# ZynqPS.net
KiCad netlist of a schematic drawn in Altium Designer
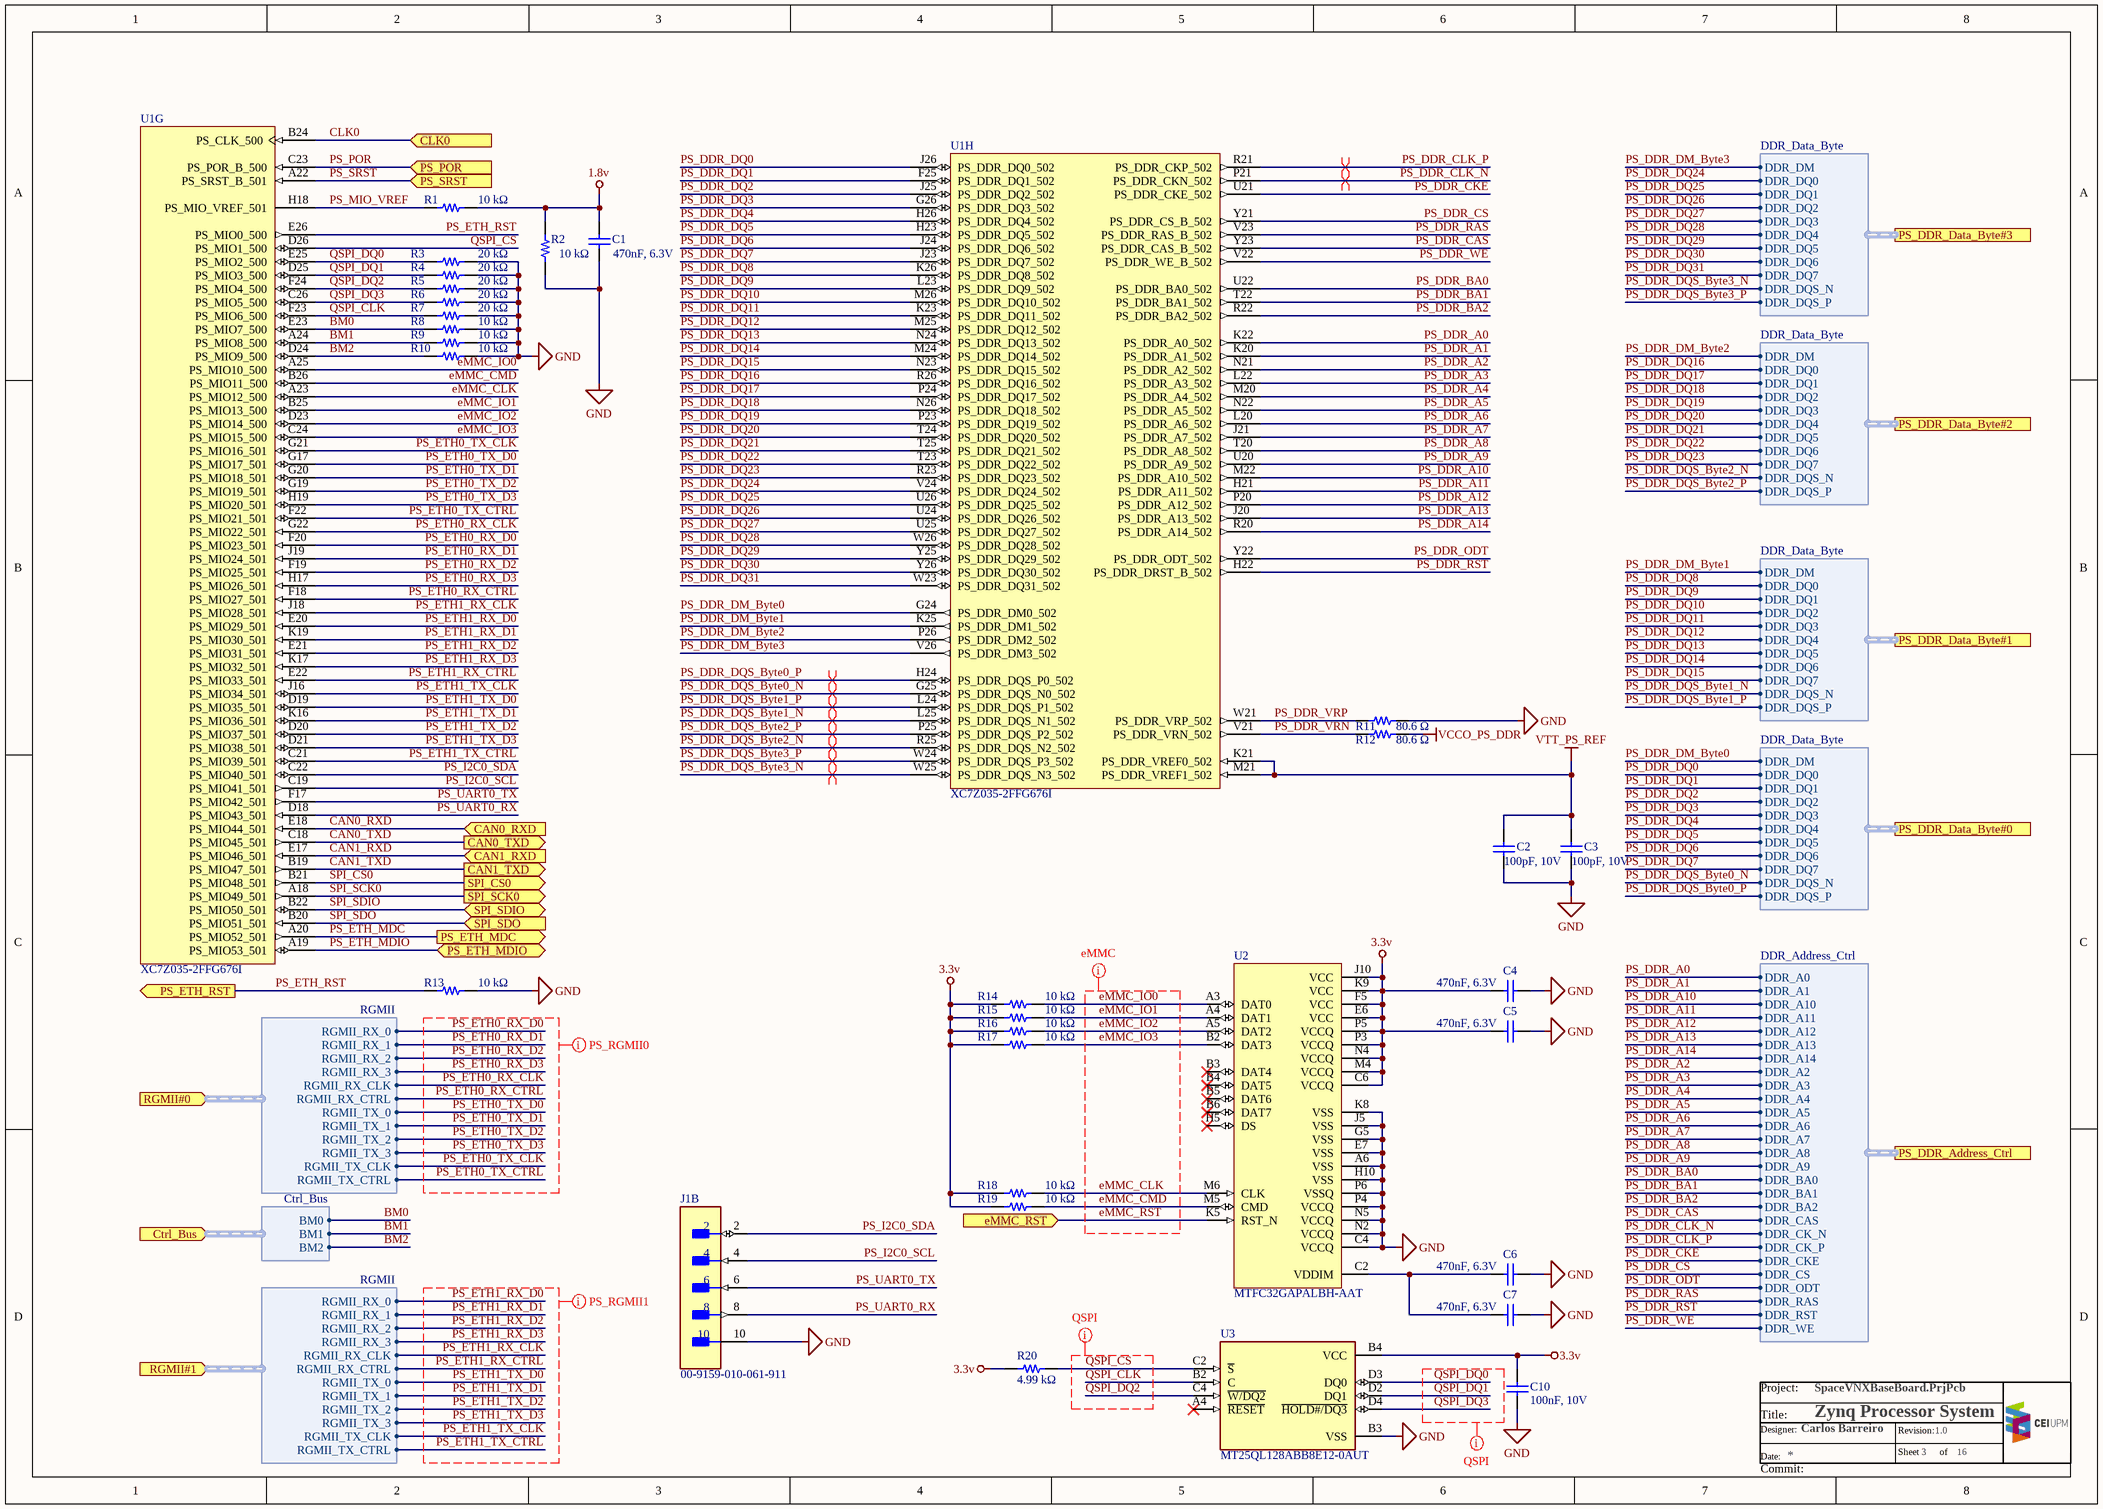
[diagram p0: ZynqPS.SchDoc]

(export (version "E")
  (design (tool "Eeschema 10.0.6"))
  (components
    (comp (ref "C1")
      (value "470nF, 6.3V")
      (footprint "WURTH_WCAP-CSGP_0402")
      (description "WCAP-CSGP Multilayer Ceramic Chip Capacitor, General Purpose, size 0402, X5R, 470nF, 6.3V")
      (fields
        (field (name "MANUFACTURER PART NUMBER") "885012105004")
        (field (name "MANUFACTURER") "Wurth Elektronik")
      )
      (libsource (lib "SpaceVNX") (part "885012105004"))
    )
    (comp (ref "C2")
      (value "100pF, 10V")
      (footprint "WURTH_WCAP-CSGP_0402")
      (description "WCAP-CSGP Multilayer Ceramic Chip Capacitor, General Purpose, size 0402, NP0, 100pF, 10V")
      (fields
        (field (name "MANUFACTURER PART NUMBER") "885012005013")
        (field (name "MANUFACTURER") "Wurth Elektronik")
      )
      (libsource (lib "SpaceVNX") (part "885012005013"))
    )
    (comp (ref "C3")
      (value "100pF, 10V")
      (footprint "WURTH_WCAP-CSGP_0402")
      (description "WCAP-CSGP Multilayer Ceramic Chip Capacitor, General Purpose, size 0402, NP0, 100pF, 10V")
      (fields
        (field (name "MANUFACTURER PART NUMBER") "885012005013")
        (field (name "MANUFACTURER") "Wurth Elektronik")
      )
      (libsource (lib "SpaceVNX") (part "885012005013"))
    )
    (comp (ref "C4")
      (value "470nF, 6.3V")
      (footprint "WURTH_WCAP-CSGP_0402")
      (description "WCAP-CSGP Multilayer Ceramic Chip Capacitor, General Purpose, size 0402, X5R, 470nF, 6.3V")
      (fields
        (field (name "MANUFACTURER PART NUMBER") "885012105004")
        (field (name "MANUFACTURER") "Wurth Elektronik")
      )
      (libsource (lib "SpaceVNX") (part "885012105004"))
    )
    (comp (ref "C5")
      (value "470nF, 6.3V")
      (footprint "WURTH_WCAP-CSGP_0402")
      (description "WCAP-CSGP Multilayer Ceramic Chip Capacitor, General Purpose, size 0402, X5R, 470nF, 6.3V")
      (fields
        (field (name "MANUFACTURER PART NUMBER") "885012105004")
        (field (name "MANUFACTURER") "Wurth Elektronik")
      )
      (libsource (lib "SpaceVNX") (part "885012105004"))
    )
    (comp (ref "C6")
      (value "470nF, 6.3V")
      (footprint "WURTH_WCAP-CSGP_0402")
      (description "WCAP-CSGP Multilayer Ceramic Chip Capacitor, General Purpose, size 0402, X5R, 470nF, 6.3V")
      (fields
        (field (name "MANUFACTURER PART NUMBER") "885012105004")
        (field (name "MANUFACTURER") "Wurth Elektronik")
      )
      (libsource (lib "SpaceVNX") (part "885012105004"))
    )
    (comp (ref "C7")
      (value "470nF, 6.3V")
      (footprint "WURTH_WCAP-CSGP_0402")
      (description "WCAP-CSGP Multilayer Ceramic Chip Capacitor, General Purpose, size 0402, X5R, 470nF, 6.3V")
      (fields
        (field (name "MANUFACTURER PART NUMBER") "885012105004")
        (field (name "MANUFACTURER") "Wurth Elektronik")
      )
      (libsource (lib "SpaceVNX") (part "885012105004"))
    )
    (comp (ref "C10")
      (value "100nF, 10V")
      (footprint "WURTH_WCAP-CSGP_0402")
      (description "WCAP-CSGP Multilayer Ceramic Chip Capacitor, General Purpose, size 0402, X7R, 100nF, 10V")
      (fields
        (field (name "MANUFACTURER PART NUMBER") "885012205018")
        (field (name "MANUFACTURER") "Wurth Elektronik")
      )
      (libsource (lib "SpaceVNX") (part "885012205018"))
    )
    (comp (ref "J1")
      (value "00-9159-010-061-911")
      (footprint "KYOCERA_00-9159-010-061-911")
      (description "Coplanar Open Ended Card Edge Connector 10 Pin")
      (libsource (lib "SpaceVNX") (part "00-9159-010-061-911"))
    )
    (comp (ref "R1")
      (value "10 kΩ")
      (footprint "PANASONIC_ERJ2G_0402")
      (description "General Purpose Thick Film Chip Resistors")
      (fields (field (name "MANUFACTURER") "Panasonic"))
      (libsource (lib "SpaceVNX") (part "ERJ2RKF1002X"))
    )
    (comp (ref "R2")
      (value "10 kΩ")
      (footprint "PANASONIC_ERJ2G_0402")
      (description "General Purpose Thick Film Chip Resistors")
      (fields (field (name "MANUFACTURER") "Panasonic"))
      (libsource (lib "SpaceVNX") (part "ERJ2RKF1002X"))
    )
    (comp (ref "R3")
      (value "20 kΩ")
      (footprint "PANASONIC_ERJ2G_0402")
      (description "General Purpose Thick Film Chip Resistors")
      (fields (field (name "MANUFACTURER") "Panasonic"))
      (libsource (lib "SpaceVNX") (part "ERJ2RKF2002X"))
    )
    (comp (ref "R4")
      (value "20 kΩ")
      (footprint "PANASONIC_ERJ2G_0402")
      (description "General Purpose Thick Film Chip Resistors")
      (fields (field (name "MANUFACTURER") "Panasonic"))
      (libsource (lib "SpaceVNX") (part "ERJ2RKF2002X"))
    )
    (comp (ref "R5")
      (value "20 kΩ")
      (footprint "PANASONIC_ERJ2G_0402")
      (description "General Purpose Thick Film Chip Resistors")
      (fields (field (name "MANUFACTURER") "Panasonic"))
      (libsource (lib "SpaceVNX") (part "ERJ2RKF2002X"))
    )
    (comp (ref "R6")
      (value "20 kΩ")
      (footprint "PANASONIC_ERJ2G_0402")
      (description "General Purpose Thick Film Chip Resistors")
      (fields (field (name "MANUFACTURER") "Panasonic"))
      (libsource (lib "SpaceVNX") (part "ERJ2RKF2002X"))
    )
    (comp (ref "R7")
      (value "20 kΩ")
      (footprint "PANASONIC_ERJ2G_0402")
      (description "General Purpose Thick Film Chip Resistors")
      (fields (field (name "MANUFACTURER") "Panasonic"))
      (libsource (lib "SpaceVNX") (part "ERJ2RKF2002X"))
    )
    (comp (ref "R8")
      (value "10 kΩ")
      (footprint "PANASONIC_ERJ2G_0402")
      (description "General Purpose Thick Film Chip Resistors")
      (fields (field (name "MANUFACTURER") "Panasonic"))
      (libsource (lib "SpaceVNX") (part "ERJ2RKF1002X"))
    )
    (comp (ref "R9")
      (value "10 kΩ")
      (footprint "PANASONIC_ERJ2G_0402")
      (description "General Purpose Thick Film Chip Resistors")
      (fields (field (name "MANUFACTURER") "Panasonic"))
      (libsource (lib "SpaceVNX") (part "ERJ2RKF1002X"))
    )
    (comp (ref "R10")
      (value "10 kΩ")
      (footprint "PANASONIC_ERJ2G_0402")
      (description "General Purpose Thick Film Chip Resistors")
      (fields (field (name "MANUFACTURER") "Panasonic"))
      (libsource (lib "SpaceVNX") (part "ERJ2RKF1002X"))
    )
    (comp (ref "R11")
      (value "80.6 Ω")
      (footprint "PANASONIC_ERJ2G_0402")
      (description "General Purpose Thick Film Chip Resistors")
      (fields (field (name "MANUFACTURER") "Panasonic"))
      (libsource (lib "SpaceVNX") (part "ERJ2RKF80R6X"))
    )
    (comp (ref "R12")
      (value "80.6 Ω")
      (footprint "PANASONIC_ERJ2G_0402")
      (description "General Purpose Thick Film Chip Resistors")
      (fields (field (name "MANUFACTURER") "Panasonic"))
      (libsource (lib "SpaceVNX") (part "ERJ2RKF80R6X"))
    )
    (comp (ref "R13")
      (value "10 kΩ")
      (footprint "PANASONIC_ERJ2G_0402")
      (description "General Purpose Thick Film Chip Resistors")
      (fields (field (name "MANUFACTURER") "Panasonic"))
      (libsource (lib "SpaceVNX") (part "ERJ2RKF1002X"))
    )
    (comp (ref "R14")
      (value "10 kΩ")
      (footprint "PANASONIC_ERJ2G_0402")
      (description "General Purpose Thick Film Chip Resistors")
      (fields (field (name "MANUFACTURER") "Panasonic"))
      (libsource (lib "SpaceVNX") (part "ERJ2RKF1002X"))
    )
    (comp (ref "R15")
      (value "10 kΩ")
      (footprint "PANASONIC_ERJ2G_0402")
      (description "General Purpose Thick Film Chip Resistors")
      (fields (field (name "MANUFACTURER") "Panasonic"))
      (libsource (lib "SpaceVNX") (part "ERJ2RKF1002X"))
    )
    (comp (ref "R16")
      (value "10 kΩ")
      (footprint "PANASONIC_ERJ2G_0402")
      (description "General Purpose Thick Film Chip Resistors")
      (fields (field (name "MANUFACTURER") "Panasonic"))
      (libsource (lib "SpaceVNX") (part "ERJ2RKF1002X"))
    )
    (comp (ref "R17")
      (value "10 kΩ")
      (footprint "PANASONIC_ERJ2G_0402")
      (description "General Purpose Thick Film Chip Resistors")
      (fields (field (name "MANUFACTURER") "Panasonic"))
      (libsource (lib "SpaceVNX") (part "ERJ2RKF1002X"))
    )
    (comp (ref "R18")
      (value "10 kΩ")
      (footprint "PANASONIC_ERJ2G_0402")
      (description "General Purpose Thick Film Chip Resistors")
      (fields (field (name "MANUFACTURER") "Panasonic"))
      (libsource (lib "SpaceVNX") (part "ERJ2RKF1002X"))
    )
    (comp (ref "R19")
      (value "10 kΩ")
      (footprint "PANASONIC_ERJ2G_0402")
      (description "General Purpose Thick Film Chip Resistors")
      (fields (field (name "MANUFACTURER") "Panasonic"))
      (libsource (lib "SpaceVNX") (part "ERJ2RKF1002X"))
    )
    (comp (ref "R20")
      (value "4.99 kΩ")
      (footprint "PANASONIC_ERJ2G_0402")
      (description "General Purpose Thick Film Chip Resistors")
      (fields (field (name "MANUFACTURER") "Panasonic"))
      (libsource (lib "SpaceVNX") (part "ERJ2RKF4991X"))
    )
    (comp (ref "U1")
      (value "XC7Z035-2FFG676I")
      (footprint "XILINX_FBG676")
      (fields (field (name "PARTNUMBER") "XC7Z035-2FBG676I") (field (name "GENERIC PART NUMBER") "XC7Z035"))
      (libsource (lib "SpaceVNX") (part "XC7Z035-2FFG676I"))
    )
    (comp (ref "U2")
      (value "MTFC32GAPALBH-AAT")
      (footprint "Micron_BH")
      (description "Flash Memory Managed NAND e.MMC Automotive 32GB")
      (fields (field (name "MF") "Micron Technology"))
      (libsource (lib "SpaceVNX") (part "MTFC32GAPALBH-AAT"))
    )
    (comp (ref "U3")
      (value "MT25QL128ABB8E12-0AUT")
      (footprint "Micron_RW")
      (description "NOR Serial Flash Memory 128Mb 3.3V Multiple I/O Automotive")
      (fields (field (name "MF") "Micron Technology"))
      (libsource (lib "SpaceVNX") (part "MT25QL128ABB8E12-0AUT"))
    )
  )
  (nets
    (net (code "5") (name "/BM0") (class "Default")
      (node (ref "R8") (pin "2") (pinfunction "2_2") (pintype "passive"))
      (node (ref "U1") (pin "E23") (pinfunction "PS_MIO7_500_E23") (pintype "bidirectional"))
    )
    (net (code "6") (name "/BM1") (class "Default")
      (node (ref "R9") (pin "2") (pinfunction "2_2") (pintype "passive"))
      (node (ref "U1") (pin "A24") (pinfunction "PS_MIO8_500_A24") (pintype "bidirectional"))
    )
    (net (code "7") (name "/BM2") (class "Default")
      (node (ref "R10") (pin "2") (pinfunction "2_2") (pintype "passive"))
      (node (ref "U1") (pin "D24") (pinfunction "PS_MIO9_500_D24") (pintype "bidirectional"))
    )
    (net (code "8") (name "/CAN0_RXD") (class "Default")
      (node (ref "U1") (pin "E18") (pinfunction "PS_MIO44_501_E18") (pintype "input"))
    )
    (net (code "9") (name "/CAN0_TXD") (class "Default")
      (node (ref "U1") (pin "C18") (pinfunction "PS_MIO45_501_C18") (pintype "output"))
    )
    (net (code "10") (name "/CAN1_RXD") (class "Default")
      (node (ref "U1") (pin "E17") (pinfunction "PS_MIO46_501_E17") (pintype "input"))
    )
    (net (code "11") (name "/CAN1_TXD") (class "Default")
      (node (ref "U1") (pin "B19") (pinfunction "PS_MIO47_501_B19") (pintype "output"))
    )
    (net (code "12") (name "/CLK0") (class "Default")
      (node (ref "U1") (pin "B24") (pinfunction "PS_CLK_500_B24") (pintype "input"))
    )
    (net (code "13") (name "/PS_DDR_A0") (class "Default")
      (node (ref "U1") (pin "K22") (pinfunction "PS_DDR_A0_502_K22") (pintype "output"))
    )
    (net (code "14") (name "/PS_DDR_A1") (class "Default")
      (node (ref "U1") (pin "K20") (pinfunction "PS_DDR_A1_502_K20") (pintype "output"))
    )
    (net (code "15") (name "/PS_DDR_A2") (class "Default")
      (node (ref "U1") (pin "N21") (pinfunction "PS_DDR_A2_502_N21") (pintype "output"))
    )
    (net (code "16") (name "/PS_DDR_A3") (class "Default")
      (node (ref "U1") (pin "L22") (pinfunction "PS_DDR_A3_502_L22") (pintype "output"))
    )
    (net (code "17") (name "/PS_DDR_A4") (class "Default")
      (node (ref "U1") (pin "M20") (pinfunction "PS_DDR_A4_502_M20") (pintype "output"))
    )
    (net (code "18") (name "/PS_DDR_A5") (class "Default")
      (node (ref "U1") (pin "N22") (pinfunction "PS_DDR_A5_502_N22") (pintype "output"))
    )
    (net (code "19") (name "/PS_DDR_A6") (class "Default")
      (node (ref "U1") (pin "L20") (pinfunction "PS_DDR_A6_502_L20") (pintype "output"))
    )
    (net (code "20") (name "/PS_DDR_A7") (class "Default")
      (node (ref "U1") (pin "J21") (pinfunction "PS_DDR_A7_502_J21") (pintype "output"))
    )
    (net (code "21") (name "/PS_DDR_A8") (class "Default")
      (node (ref "U1") (pin "T20") (pinfunction "PS_DDR_A8_502_T20") (pintype "output"))
    )
    (net (code "22") (name "/PS_DDR_A9") (class "Default")
      (node (ref "U1") (pin "U20") (pinfunction "PS_DDR_A9_502_U20") (pintype "output"))
    )
    (net (code "23") (name "/PS_DDR_A10") (class "Default")
      (node (ref "U1") (pin "M22") (pinfunction "PS_DDR_A10_502_M22") (pintype "output"))
    )
    (net (code "24") (name "/PS_DDR_A11") (class "Default")
      (node (ref "U1") (pin "H21") (pinfunction "PS_DDR_A11_502_H21") (pintype "output"))
    )
    (net (code "25") (name "/PS_DDR_A12") (class "Default")
      (node (ref "U1") (pin "P20") (pinfunction "PS_DDR_A12_502_P20") (pintype "output"))
    )
    (net (code "26") (name "/PS_DDR_A13") (class "Default")
      (node (ref "U1") (pin "J20") (pinfunction "PS_DDR_A13_502_J20") (pintype "output"))
    )
    (net (code "27") (name "/PS_DDR_A14") (class "Default")
      (node (ref "U1") (pin "R20") (pinfunction "PS_DDR_A14_502_R20") (pintype "output"))
    )
    (net (code "28") (name "/PS_DDR_BA0") (class "Default")
      (node (ref "U1") (pin "U22") (pinfunction "PS_DDR_BA0_502_U22") (pintype "output"))
    )
    (net (code "29") (name "/PS_DDR_BA1") (class "Default")
      (node (ref "U1") (pin "T22") (pinfunction "PS_DDR_BA1_502_T22") (pintype "output"))
    )
    (net (code "30") (name "/PS_DDR_BA2") (class "Default")
      (node (ref "U1") (pin "R22") (pinfunction "PS_DDR_BA2_502_R22") (pintype "output"))
    )
    (net (code "31") (name "/PS_DDR_CAS") (class "Default")
      (node (ref "U1") (pin "Y23") (pinfunction "PS_DDR_CAS_B_502_Y23") (pintype "output"))
    )
    (net (code "32") (name "/PS_DDR_CKE") (class "Default")
      (node (ref "U1") (pin "U21") (pinfunction "PS_DDR_CKE_502_U21") (pintype "output"))
    )
    (net (code "33") (name "/PS_DDR_CLK_N") (class "Default")
      (node (ref "U1") (pin "P21") (pinfunction "PS_DDR_CKN_502_P21") (pintype "output"))
    )
    (net (code "34") (name "/PS_DDR_CLK_P") (class "Default")
      (node (ref "U1") (pin "R21") (pinfunction "PS_DDR_CKP_502_R21") (pintype "output"))
    )
    (net (code "35") (name "/PS_DDR_CS") (class "Default")
      (node (ref "U1") (pin "Y21") (pinfunction "PS_DDR_CS_B_502_Y21") (pintype "output"))
    )
    (net (code "36") (name "/PS_DDR_DM_Byte0") (class "Default")
      (node (ref "U1") (pin "G24") (pinfunction "PS_DDR_DM0_502_G24") (pintype "output"))
    )
    (net (code "37") (name "/PS_DDR_DM_Byte1") (class "Default")
      (node (ref "U1") (pin "K25") (pinfunction "PS_DDR_DM1_502_K25") (pintype "output"))
    )
    (net (code "38") (name "/PS_DDR_DM_Byte2") (class "Default")
      (node (ref "U1") (pin "P26") (pinfunction "PS_DDR_DM2_502_P26") (pintype "output"))
    )
    (net (code "39") (name "/PS_DDR_DM_Byte3") (class "Default")
      (node (ref "U1") (pin "V26") (pinfunction "PS_DDR_DM3_502_V26") (pintype "output"))
    )
    (net (code "40") (name "/PS_DDR_DQ0") (class "Default")
      (node (ref "U1") (pin "J26") (pinfunction "PS_DDR_DQ0_502_J26") (pintype "bidirectional"))
    )
    (net (code "41") (name "/PS_DDR_DQ1") (class "Default")
      (node (ref "U1") (pin "F25") (pinfunction "PS_DDR_DQ1_502_F25") (pintype "bidirectional"))
    )
    (net (code "42") (name "/PS_DDR_DQ2") (class "Default")
      (node (ref "U1") (pin "J25") (pinfunction "PS_DDR_DQ2_502_J25") (pintype "bidirectional"))
    )
    (net (code "43") (name "/PS_DDR_DQ3") (class "Default")
      (node (ref "U1") (pin "G26") (pinfunction "PS_DDR_DQ3_502_G26") (pintype "bidirectional"))
    )
    (net (code "44") (name "/PS_DDR_DQ4") (class "Default")
      (node (ref "U1") (pin "H26") (pinfunction "PS_DDR_DQ4_502_H26") (pintype "bidirectional"))
    )
    (net (code "45") (name "/PS_DDR_DQ5") (class "Default")
      (node (ref "U1") (pin "H23") (pinfunction "PS_DDR_DQ5_502_H23") (pintype "bidirectional"))
    )
    (net (code "46") (name "/PS_DDR_DQ6") (class "Default")
      (node (ref "U1") (pin "J24") (pinfunction "PS_DDR_DQ6_502_J24") (pintype "bidirectional"))
    )
    (net (code "47") (name "/PS_DDR_DQ7") (class "Default")
      (node (ref "U1") (pin "J23") (pinfunction "PS_DDR_DQ7_502_J23") (pintype "bidirectional"))
    )
    (net (code "48") (name "/PS_DDR_DQ8") (class "Default")
      (node (ref "U1") (pin "K26") (pinfunction "PS_DDR_DQ8_502_K26") (pintype "bidirectional"))
    )
    (net (code "49") (name "/PS_DDR_DQ9") (class "Default")
      (node (ref "U1") (pin "L23") (pinfunction "PS_DDR_DQ9_502_L23") (pintype "bidirectional"))
    )
    (net (code "50") (name "/PS_DDR_DQ10") (class "Default")
      (node (ref "U1") (pin "M26") (pinfunction "PS_DDR_DQ10_502_M26") (pintype "bidirectional"))
    )
    (net (code "51") (name "/PS_DDR_DQ11") (class "Default")
      (node (ref "U1") (pin "K23") (pinfunction "PS_DDR_DQ11_502_K23") (pintype "bidirectional"))
    )
    (net (code "52") (name "/PS_DDR_DQ12") (class "Default")
      (node (ref "U1") (pin "M25") (pinfunction "PS_DDR_DQ12_502_M25") (pintype "bidirectional"))
    )
    (net (code "53") (name "/PS_DDR_DQ13") (class "Default")
      (node (ref "U1") (pin "N24") (pinfunction "PS_DDR_DQ13_502_N24") (pintype "bidirectional"))
    )
    (net (code "54") (name "/PS_DDR_DQ14") (class "Default")
      (node (ref "U1") (pin "M24") (pinfunction "PS_DDR_DQ14_502_M24") (pintype "bidirectional"))
    )
    (net (code "55") (name "/PS_DDR_DQ15") (class "Default")
      (node (ref "U1") (pin "N23") (pinfunction "PS_DDR_DQ15_502_N23") (pintype "bidirectional"))
    )
    (net (code "56") (name "/PS_DDR_DQ16") (class "Default")
      (node (ref "U1") (pin "R26") (pinfunction "PS_DDR_DQ16_502_R26") (pintype "bidirectional"))
    )
    (net (code "57") (name "/PS_DDR_DQ17") (class "Default")
      (node (ref "U1") (pin "P24") (pinfunction "PS_DDR_DQ17_502_P24") (pintype "bidirectional"))
    )
    (net (code "58") (name "/PS_DDR_DQ18") (class "Default")
      (node (ref "U1") (pin "N26") (pinfunction "PS_DDR_DQ18_502_N26") (pintype "bidirectional"))
    )
    (net (code "59") (name "/PS_DDR_DQ19") (class "Default")
      (node (ref "U1") (pin "P23") (pinfunction "PS_DDR_DQ19_502_P23") (pintype "bidirectional"))
    )
    (net (code "60") (name "/PS_DDR_DQ20") (class "Default")
      (node (ref "U1") (pin "T24") (pinfunction "PS_DDR_DQ20_502_T24") (pintype "bidirectional"))
    )
    (net (code "61") (name "/PS_DDR_DQ21") (class "Default")
      (node (ref "U1") (pin "T25") (pinfunction "PS_DDR_DQ21_502_T25") (pintype "bidirectional"))
    )
    (net (code "62") (name "/PS_DDR_DQ22") (class "Default")
      (node (ref "U1") (pin "T23") (pinfunction "PS_DDR_DQ22_502_T23") (pintype "bidirectional"))
    )
    (net (code "63") (name "/PS_DDR_DQ23") (class "Default")
      (node (ref "U1") (pin "R23") (pinfunction "PS_DDR_DQ23_502_R23") (pintype "bidirectional"))
    )
    (net (code "64") (name "/PS_DDR_DQ24") (class "Default")
      (node (ref "U1") (pin "V24") (pinfunction "PS_DDR_DQ24_502_V24") (pintype "bidirectional"))
    )
    (net (code "65") (name "/PS_DDR_DQ25") (class "Default")
      (node (ref "U1") (pin "U26") (pinfunction "PS_DDR_DQ25_502_U26") (pintype "bidirectional"))
    )
    (net (code "66") (name "/PS_DDR_DQ26") (class "Default")
      (node (ref "U1") (pin "U24") (pinfunction "PS_DDR_DQ26_502_U24") (pintype "bidirectional"))
    )
    (net (code "67") (name "/PS_DDR_DQ27") (class "Default")
      (node (ref "U1") (pin "U25") (pinfunction "PS_DDR_DQ27_502_U25") (pintype "bidirectional"))
    )
    (net (code "68") (name "/PS_DDR_DQ28") (class "Default")
      (node (ref "U1") (pin "W26") (pinfunction "PS_DDR_DQ28_502_W26") (pintype "bidirectional"))
    )
    (net (code "69") (name "/PS_DDR_DQ29") (class "Default")
      (node (ref "U1") (pin "Y25") (pinfunction "PS_DDR_DQ29_502_Y25") (pintype "bidirectional"))
    )
    (net (code "70") (name "/PS_DDR_DQ30") (class "Default")
      (node (ref "U1") (pin "Y26") (pinfunction "PS_DDR_DQ30_502_Y26") (pintype "bidirectional"))
    )
    (net (code "71") (name "/PS_DDR_DQ31") (class "Default")
      (node (ref "U1") (pin "W23") (pinfunction "PS_DDR_DQ31_502_W23") (pintype "bidirectional"))
    )
    (net (code "72") (name "/PS_DDR_DQS_Byte0_N") (class "Default")
      (node (ref "U1") (pin "G25") (pinfunction "PS_DDR_DQS_N0_502_G25") (pintype "bidirectional"))
    )
    (net (code "73") (name "/PS_DDR_DQS_Byte0_P") (class "Default")
      (node (ref "U1") (pin "H24") (pinfunction "PS_DDR_DQS_P0_502_H24") (pintype "bidirectional"))
    )
    (net (code "74") (name "/PS_DDR_DQS_Byte1_N") (class "Default")
      (node (ref "U1") (pin "L25") (pinfunction "PS_DDR_DQS_N1_502_L25") (pintype "bidirectional"))
    )
    (net (code "75") (name "/PS_DDR_DQS_Byte1_P") (class "Default")
      (node (ref "U1") (pin "L24") (pinfunction "PS_DDR_DQS_P1_502_L24") (pintype "bidirectional"))
    )
    (net (code "76") (name "/PS_DDR_DQS_Byte2_N") (class "Default")
      (node (ref "U1") (pin "R25") (pinfunction "PS_DDR_DQS_N2_502_R25") (pintype "bidirectional"))
    )
    (net (code "77") (name "/PS_DDR_DQS_Byte2_P") (class "Default")
      (node (ref "U1") (pin "P25") (pinfunction "PS_DDR_DQS_P2_502_P25") (pintype "bidirectional"))
    )
    (net (code "78") (name "/PS_DDR_DQS_Byte3_N") (class "Default")
      (node (ref "U1") (pin "W25") (pinfunction "PS_DDR_DQS_N3_502_W25") (pintype "bidirectional"))
    )
    (net (code "79") (name "/PS_DDR_DQS_Byte3_P") (class "Default")
      (node (ref "U1") (pin "W24") (pinfunction "PS_DDR_DQS_P3_502_W24") (pintype "bidirectional"))
    )
    (net (code "80") (name "/PS_DDR_ODT") (class "Default")
      (node (ref "U1") (pin "Y22") (pinfunction "PS_DDR_ODT_502_Y22") (pintype "output"))
    )
    (net (code "81") (name "/PS_DDR_RAS") (class "Default")
      (node (ref "U1") (pin "V23") (pinfunction "PS_DDR_RAS_B_502_V23") (pintype "output"))
    )
    (net (code "82") (name "/PS_DDR_RST") (class "Default")
      (node (ref "U1") (pin "H22") (pinfunction "PS_DDR_DRST_B_502_H22") (pintype "output"))
    )
    (net (code "83") (name "/PS_DDR_VRN") (class "Default")
      (node (ref "R12") (pin "1") (pinfunction "1_1") (pintype "passive"))
      (node (ref "U1") (pin "V21") (pinfunction "PS_DDR_VRN_502_V21") (pintype "output"))
    )
    (net (code "84") (name "/PS_DDR_VRP") (class "Default")
      (node (ref "R11") (pin "1") (pinfunction "1_1") (pintype "passive"))
      (node (ref "U1") (pin "W21") (pinfunction "PS_DDR_VRP_502_W21") (pintype "output"))
    )
    (net (code "85") (name "/PS_DDR_WE") (class "Default")
      (node (ref "U1") (pin "V22") (pinfunction "PS_DDR_WE_B_502_V22") (pintype "output"))
    )
    (net (code "86") (name "/PS_ETH0_RX_CLK") (class "Default")
      (node (ref "U1") (pin "G22") (pinfunction "PS_MIO22_501_G22") (pintype "input"))
    )
    (net (code "87") (name "/PS_ETH0_RX_CTRL") (class "Default")
      (node (ref "U1") (pin "F18") (pinfunction "PS_MIO27_501_F18") (pintype "input"))
    )
    (net (code "88") (name "/PS_ETH0_RX_D0") (class "Default")
      (node (ref "U1") (pin "F20") (pinfunction "PS_MIO23_501_F20") (pintype "input"))
    )
    (net (code "89") (name "/PS_ETH0_RX_D1") (class "Default")
      (node (ref "U1") (pin "J19") (pinfunction "PS_MIO24_501_J19") (pintype "input"))
    )
    (net (code "90") (name "/PS_ETH0_RX_D2") (class "Default")
      (node (ref "U1") (pin "F19") (pinfunction "PS_MIO25_501_F19") (pintype "input"))
    )
    (net (code "91") (name "/PS_ETH0_RX_D3") (class "Default")
      (node (ref "U1") (pin "H17") (pinfunction "PS_MIO26_501_H17") (pintype "input"))
    )
    (net (code "92") (name "/PS_ETH0_TX_CLK") (class "Default")
      (node (ref "U1") (pin "G21") (pinfunction "PS_MIO16_501_G21") (pintype "bidirectional"))
    )
    (net (code "93") (name "/PS_ETH0_TX_CTRL") (class "Default")
      (node (ref "U1") (pin "F22") (pinfunction "PS_MIO21_501_F22") (pintype "bidirectional"))
    )
    (net (code "94") (name "/PS_ETH0_TX_D0") (class "Default")
      (node (ref "U1") (pin "G17") (pinfunction "PS_MIO17_501_G17") (pintype "bidirectional"))
    )
    (net (code "95") (name "/PS_ETH0_TX_D1") (class "Default")
      (node (ref "U1") (pin "G20") (pinfunction "PS_MIO18_501_G20") (pintype "bidirectional"))
    )
    (net (code "96") (name "/PS_ETH0_TX_D2") (class "Default")
      (node (ref "U1") (pin "G19") (pinfunction "PS_MIO19_501_G19") (pintype "bidirectional"))
    )
    (net (code "97") (name "/PS_ETH0_TX_D3") (class "Default")
      (node (ref "U1") (pin "H19") (pinfunction "PS_MIO20_501_H19") (pintype "bidirectional"))
    )
    (net (code "98") (name "/PS_ETH1_RX_CLK") (class "Default")
      (node (ref "U1") (pin "J18") (pinfunction "PS_MIO28_501_J18") (pintype "input"))
    )
    (net (code "99") (name "/PS_ETH1_RX_CTRL") (class "Default")
      (node (ref "U1") (pin "E22") (pinfunction "PS_MIO33_501_E22") (pintype "input"))
    )
    (net (code "100") (name "/PS_ETH1_RX_D0") (class "Default")
      (node (ref "U1") (pin "E20") (pinfunction "PS_MIO29_501_E20") (pintype "input"))
    )
    (net (code "101") (name "/PS_ETH1_RX_D1") (class "Default")
      (node (ref "U1") (pin "K19") (pinfunction "PS_MIO30_501_K19") (pintype "input"))
    )
    (net (code "102") (name "/PS_ETH1_RX_D2") (class "Default")
      (node (ref "U1") (pin "E21") (pinfunction "PS_MIO31_501_E21") (pintype "input"))
    )
    (net (code "103") (name "/PS_ETH1_RX_D3") (class "Default")
      (node (ref "U1") (pin "K17") (pinfunction "PS_MIO32_501_K17") (pintype "input"))
    )
    (net (code "104") (name "/PS_ETH1_TX_CLK") (class "Default")
      (node (ref "U1") (pin "J16") (pinfunction "PS_MIO34_501_J16") (pintype "bidirectional"))
    )
    (net (code "105") (name "/PS_ETH1_TX_CTRL") (class "Default")
      (node (ref "U1") (pin "C21") (pinfunction "PS_MIO39_501_C21") (pintype "bidirectional"))
    )
    (net (code "106") (name "/PS_ETH1_TX_D0") (class "Default")
      (node (ref "U1") (pin "D19") (pinfunction "PS_MIO35_501_D19") (pintype "bidirectional"))
    )
    (net (code "107") (name "/PS_ETH1_TX_D1") (class "Default")
      (node (ref "U1") (pin "K16") (pinfunction "PS_MIO36_501_K16") (pintype "bidirectional"))
    )
    (net (code "108") (name "/PS_ETH1_TX_D2") (class "Default")
      (node (ref "U1") (pin "D20") (pinfunction "PS_MIO37_501_D20") (pintype "bidirectional"))
    )
    (net (code "109") (name "/PS_ETH1_TX_D3") (class "Default")
      (node (ref "U1") (pin "D21") (pinfunction "PS_MIO38_501_D21") (pintype "bidirectional"))
    )
    (net (code "110") (name "/PS_ETH_MDC") (class "Default")
      (node (ref "U1") (pin "A20") (pinfunction "PS_MIO52_501_A20") (pintype "output"))
    )
    (net (code "111") (name "/PS_ETH_MDIO") (class "Default")
      (node (ref "U1") (pin "A19") (pinfunction "PS_MIO53_501_A19") (pintype "bidirectional"))
    )
    (net (code "112") (name "/PS_ETH_RST") (class "Default")
      (node (ref "R13") (pin "2") (pinfunction "2_2") (pintype "passive"))
      (node (ref "U1") (pin "E26") (pinfunction "PS_MIO0_500_E26") (pintype "output"))
    )
    (net (code "113") (name "/PS_I2C0_SCL") (class "Default")
      (node (ref "J1") (pin "4") (pinfunction "4_4") (pintype "input"))
      (node (ref "U1") (pin "C19") (pinfunction "PS_MIO41_501_C19") (pintype "output"))
    )
    (net (code "114") (name "/PS_I2C0_SDA") (class "Default")
      (node (ref "J1") (pin "2") (pinfunction "2_2") (pintype "bidirectional"))
      (node (ref "U1") (pin "C22") (pinfunction "PS_MIO40_501_C22") (pintype "bidirectional"))
    )
    (net (code "115") (name "/PS_MIO_VREF") (class "Default")
      (node (ref "R1") (pin "2") (pinfunction "2_2") (pintype "passive"))
      (node (ref "U1") (pin "H18") (pinfunction "PS_MIO_VREF_501_H18") (pintype "passive"))
    )
    (net (code "116") (name "/PS_POR") (class "Default")
      (node (ref "U1") (pin "C23") (pinfunction "PS_POR_B_500_C23") (pintype "input"))
    )
    (net (code "117") (name "/PS_SRST") (class "Default")
      (node (ref "U1") (pin "A22") (pinfunction "PS_SRST_B_501_A22") (pintype "input"))
    )
    (net (code "118") (name "/PS_UART0_RX") (class "Default")
      (node (ref "J1") (pin "8") (pinfunction "8_8") (pintype "output"))
      (node (ref "U1") (pin "D18") (pinfunction "PS_MIO43_501_D18") (pintype "input"))
    )
    (net (code "119") (name "/PS_UART0_TX") (class "Default")
      (node (ref "J1") (pin "6") (pinfunction "6_6") (pintype "input"))
      (node (ref "U1") (pin "F17") (pinfunction "PS_MIO42_501_F17") (pintype "output"))
    )
    (net (code "120") (name "/QSPI_CLK") (class "Default")
      (node (ref "R7") (pin "1") (pinfunction "1_1") (pintype "passive"))
      (node (ref "U1") (pin "F23") (pinfunction "PS_MIO6_500_F23") (pintype "bidirectional"))
      (node (ref "U3") (pin "B2") (pinfunction "C_B2") (pintype "input"))
    )
    (net (code "121") (name "/QSPI_CS") (class "Default")
      (node (ref "R20") (pin "2") (pinfunction "2_2") (pintype "passive"))
      (node (ref "U1") (pin "D26") (pinfunction "PS_MIO1_500_D26") (pintype "bidirectional"))
      (node (ref "U3") (pin "C2") (pinfunction "~{S}_C2") (pintype "input"))
    )
    (net (code "122") (name "/QSPI_DQ0") (class "Default")
      (node (ref "R3") (pin "1") (pinfunction "1_1") (pintype "passive"))
      (node (ref "U1") (pin "E25") (pinfunction "PS_MIO2_500_E25") (pintype "bidirectional"))
      (node (ref "U3") (pin "D3") (pinfunction "DQ0_D3") (pintype "bidirectional"))
    )
    (net (code "123") (name "/QSPI_DQ1") (class "Default")
      (node (ref "R4") (pin "1") (pinfunction "1_1") (pintype "passive"))
      (node (ref "U1") (pin "D25") (pinfunction "PS_MIO3_500_D25") (pintype "bidirectional"))
      (node (ref "U3") (pin "D2") (pinfunction "DQ1_D2") (pintype "bidirectional"))
    )
    (net (code "124") (name "/QSPI_DQ2") (class "Default")
      (node (ref "R5") (pin "1") (pinfunction "1_1") (pintype "passive"))
      (node (ref "U1") (pin "F24") (pinfunction "PS_MIO4_500_F24") (pintype "bidirectional"))
      (node (ref "U3") (pin "C4") (pinfunction "~{W/DQ2}_C4") (pintype "input"))
    )
    (net (code "125") (name "/QSPI_DQ3") (class "Default")
      (node (ref "R6") (pin "1") (pinfunction "1_1") (pintype "passive"))
      (node (ref "U1") (pin "C26") (pinfunction "PS_MIO5_500_C26") (pintype "bidirectional"))
      (node (ref "U3") (pin "D4") (pinfunction "~{HOLD#/DQ3}_D4") (pintype "bidirectional"))
    )
    (net (code "126") (name "/SPI_CS0") (class "Default")
      (node (ref "U1") (pin "B21") (pinfunction "PS_MIO48_501_B21") (pintype "output"))
    )
    (net (code "127") (name "/SPI_SCK0") (class "Default")
      (node (ref "U1") (pin "A18") (pinfunction "PS_MIO49_501_A18") (pintype "output"))
    )
    (net (code "128") (name "/SPI_SDIO") (class "Default")
      (node (ref "U1") (pin "B22") (pinfunction "PS_MIO50_501_B22") (pintype "bidirectional"))
    )
    (net (code "129") (name "/SPI_SDO") (class "Default")
      (node (ref "U1") (pin "B20") (pinfunction "PS_MIO51_501_B20") (pintype "input"))
    )
    (net (code "130") (name "/eMMC_CLK") (class "Default")
      (node (ref "R18") (pin "1") (pinfunction "1_1") (pintype "passive"))
      (node (ref "U1") (pin "A23") (pinfunction "PS_MIO12_500_A23") (pintype "bidirectional"))
      (node (ref "U2") (pin "M6") (pinfunction "CLK_M6") (pintype "input"))
    )
    (net (code "131") (name "/eMMC_CMD") (class "Default")
      (node (ref "R19") (pin "1") (pinfunction "1_1") (pintype "passive"))
      (node (ref "U1") (pin "B26") (pinfunction "PS_MIO11_500_B26") (pintype "bidirectional"))
      (node (ref "U2") (pin "M5") (pinfunction "CMD_M5") (pintype "bidirectional"))
    )
    (net (code "132") (name "/eMMC_IO0") (class "Default")
      (node (ref "R14") (pin "1") (pinfunction "1_1") (pintype "passive"))
      (node (ref "U1") (pin "A25") (pinfunction "PS_MIO10_500_A25") (pintype "bidirectional"))
      (node (ref "U2") (pin "A3") (pinfunction "DAT0_A3") (pintype "bidirectional"))
    )
    (net (code "133") (name "/eMMC_IO1") (class "Default")
      (node (ref "R15") (pin "1") (pinfunction "1_1") (pintype "passive"))
      (node (ref "U1") (pin "B25") (pinfunction "PS_MIO13_500_B25") (pintype "bidirectional"))
      (node (ref "U2") (pin "A4") (pinfunction "DAT1_A4") (pintype "bidirectional"))
    )
    (net (code "134") (name "/eMMC_IO2") (class "Default")
      (node (ref "R16") (pin "1") (pinfunction "1_1") (pintype "passive"))
      (node (ref "U1") (pin "D23") (pinfunction "PS_MIO14_500_D23") (pintype "bidirectional"))
      (node (ref "U2") (pin "A5") (pinfunction "DAT2_A5") (pintype "bidirectional"))
    )
    (net (code "135") (name "/eMMC_IO3") (class "Default")
      (node (ref "R17") (pin "1") (pinfunction "1_1") (pintype "passive"))
      (node (ref "U1") (pin "C24") (pinfunction "PS_MIO15_500_C24") (pintype "bidirectional"))
      (node (ref "U2") (pin "B2") (pinfunction "DAT3_B2") (pintype "bidirectional"))
    )
    (net (code "136") (name "/eMMC_RST") (class "Default")
      (node (ref "U2") (pin "K5") (pinfunction "RST_N_K5") (pintype "input"))
    )
    (net (code "141") (name "1.8v") (class "Default")
      (node (ref "C1") (pin "1") (pinfunction "1_1") (pintype "passive"))
      (node (ref "R1") (pin "1") (pinfunction "1_1") (pintype "passive"))
      (node (ref "R2") (pin "2") (pinfunction "2_2") (pintype "passive"))
    )
    (net (code "142") (name "3.3v") (class "Default")
      (node (ref "C10") (pin "2") (pinfunction "2_2") (pintype "passive"))
      (node (ref "C4") (pin "1") (pinfunction "1_1") (pintype "passive"))
      (node (ref "C5") (pin "1") (pinfunction "1_1") (pintype "passive"))
      (node (ref "R14") (pin "2") (pinfunction "2_2") (pintype "passive"))
      (node (ref "R15") (pin "2") (pinfunction "2_2") (pintype "passive"))
      (node (ref "R16") (pin "2") (pinfunction "2_2") (pintype "passive"))
      (node (ref "R17") (pin "2") (pinfunction "2_2") (pintype "passive"))
      (node (ref "R18") (pin "2") (pinfunction "2_2") (pintype "passive"))
      (node (ref "R19") (pin "2") (pinfunction "2_2") (pintype "passive"))
      (node (ref "R20") (pin "1") (pinfunction "1_1") (pintype "passive"))
      (node (ref "U2") (pin "C6") (pinfunction "VCCQ_C6") (pintype "power_in"))
      (node (ref "U2") (pin "E6") (pinfunction "VCC_E6") (pintype "power_in"))
      (node (ref "U2") (pin "F5") (pinfunction "VCC_F5") (pintype "power_in"))
      (node (ref "U2") (pin "J10") (pinfunction "VCC_J10") (pintype "power_in"))
      (node (ref "U2") (pin "K9") (pinfunction "VCC_K9") (pintype "power_in"))
      (node (ref "U2") (pin "M4") (pinfunction "VCCQ_M4") (pintype "power_in"))
      (node (ref "U2") (pin "N4") (pinfunction "VCCQ_N4") (pintype "power_in"))
      (node (ref "U2") (pin "P3") (pinfunction "VCCQ_P3") (pintype "power_in"))
      (node (ref "U2") (pin "P5") (pinfunction "VCCQ_P5") (pintype "power_in"))
      (node (ref "U3") (pin "B4") (pinfunction "VCC_B4") (pintype "power_in"))
    )
    (net (code "143") (name "GND") (class "Default")
      (node (ref "C1") (pin "2") (pinfunction "2_2") (pintype "passive"))
      (node (ref "C10") (pin "1") (pinfunction "1_1") (pintype "passive"))
      (node (ref "C2") (pin "1") (pinfunction "1_1") (pintype "passive"))
      (node (ref "C3") (pin "1") (pinfunction "1_1") (pintype "passive"))
      (node (ref "C4") (pin "2") (pinfunction "2_2") (pintype "passive"))
      (node (ref "C5") (pin "2") (pinfunction "2_2") (pintype "passive"))
      (node (ref "C6") (pin "2") (pinfunction "2_2") (pintype "passive"))
      (node (ref "C7") (pin "2") (pinfunction "2_2") (pintype "passive"))
      (node (ref "J1") (pin "10") (pinfunction "10_10") (pintype "passive"))
      (node (ref "R10") (pin "1") (pinfunction "1_1") (pintype "passive"))
      (node (ref "R11") (pin "2") (pinfunction "2_2") (pintype "passive"))
      (node (ref "R13") (pin "1") (pinfunction "1_1") (pintype "passive"))
      (node (ref "R2") (pin "1") (pinfunction "1_1") (pintype "passive"))
      (node (ref "R3") (pin "2") (pinfunction "2_2") (pintype "passive"))
      (node (ref "R4") (pin "2") (pinfunction "2_2") (pintype "passive"))
      (node (ref "R5") (pin "2") (pinfunction "2_2") (pintype "passive"))
      (node (ref "R6") (pin "2") (pinfunction "2_2") (pintype "passive"))
      (node (ref "R7") (pin "2") (pinfunction "2_2") (pintype "passive"))
      (node (ref "R8") (pin "1") (pinfunction "1_1") (pintype "passive"))
      (node (ref "R9") (pin "1") (pinfunction "1_1") (pintype "passive"))
      (node (ref "U2") (pin "A6") (pinfunction "VSS_A6") (pintype "power_in"))
      (node (ref "U2") (pin "C4") (pinfunction "VCCQ_C4") (pintype "power_in"))
      (node (ref "U2") (pin "E7") (pinfunction "VSS_E7") (pintype "power_in"))
      (node (ref "U2") (pin "G5") (pinfunction "VSS_G5") (pintype "power_in"))
      (node (ref "U2") (pin "H10") (pinfunction "VSS_H10") (pintype "power_in"))
      (node (ref "U2") (pin "J5") (pinfunction "VSS_J5") (pintype "power_in"))
      (node (ref "U2") (pin "K8") (pinfunction "VSS_K8") (pintype "power_in"))
      (node (ref "U2") (pin "N2") (pinfunction "VCCQ_N2") (pintype "power_in"))
      (node (ref "U2") (pin "N5") (pinfunction "VCCQ_N5") (pintype "power_in"))
      (node (ref "U2") (pin "P4") (pinfunction "VCCQ_P4") (pintype "power_in"))
      (node (ref "U2") (pin "P6") (pinfunction "VSSQ_P6") (pintype "power_in"))
      (node (ref "U3") (pin "B3") (pinfunction "VSS_B3") (pintype "power_in"))
    )
    (net (code "144") (name "Net-(U2-VDDIM)") (class "Default")
      (node (ref "C6") (pin "1") (pinfunction "1_1") (pintype "passive"))
      (node (ref "C7") (pin "1") (pinfunction "1_1") (pintype "passive"))
      (node (ref "U2") (pin "C2") (pinfunction "VDDIM_C2") (pintype "power_in"))
    )
    (net (code "145") (name "VCCO_PS_DDR") (class "Default")
      (node (ref "R12") (pin "2") (pinfunction "2_2") (pintype "passive"))
    )
    (net (code "146") (name "VTT_PS_REF") (class "Default")
      (node (ref "C2") (pin "2") (pinfunction "2_2") (pintype "passive"))
      (node (ref "C3") (pin "2") (pinfunction "2_2") (pintype "passive"))
      (node (ref "U1") (pin "K21") (pinfunction "PS_DDR_VREF0_502_K21") (pintype "input"))
      (node (ref "U1") (pin "M21") (pinfunction "PS_DDR_VREF1_502_M21") (pintype "input"))
    )
    (net (code "147") (name "unconnected-(U2-DAT4-PadB3)") (class "Default")
      (node (ref "U2") (pin "B3") (pinfunction "DAT4_B3") (pintype "bidirectional+no_connect"))
    )
    (net (code "148") (name "unconnected-(U2-DAT5-PadB4)") (class "Default")
      (node (ref "U2") (pin "B4") (pinfunction "DAT5_B4") (pintype "bidirectional+no_connect"))
    )
    (net (code "149") (name "unconnected-(U2-DAT6-PadB5)") (class "Default")
      (node (ref "U2") (pin "B5") (pinfunction "DAT6_B5") (pintype "bidirectional+no_connect"))
    )
    (net (code "150") (name "unconnected-(U2-DAT7-PadB6)") (class "Default")
      (node (ref "U2") (pin "B6") (pinfunction "DAT7_B6") (pintype "bidirectional+no_connect"))
    )
    (net (code "151") (name "unconnected-(U2-DS-PadH5)") (class "Default")
      (node (ref "U2") (pin "H5") (pinfunction "DS_H5") (pintype "bidirectional+no_connect"))
    )
    (net (code "152") (name "unconnected-(U3-~{RESET}-PadA4)") (class "Default")
      (node (ref "U3") (pin "A4") (pinfunction "~{RESET}_A4") (pintype "input+no_connect"))
    )
  )
)
